# FloppyController1A.net
KiCad netlist of a schematic drawn in EAGLE
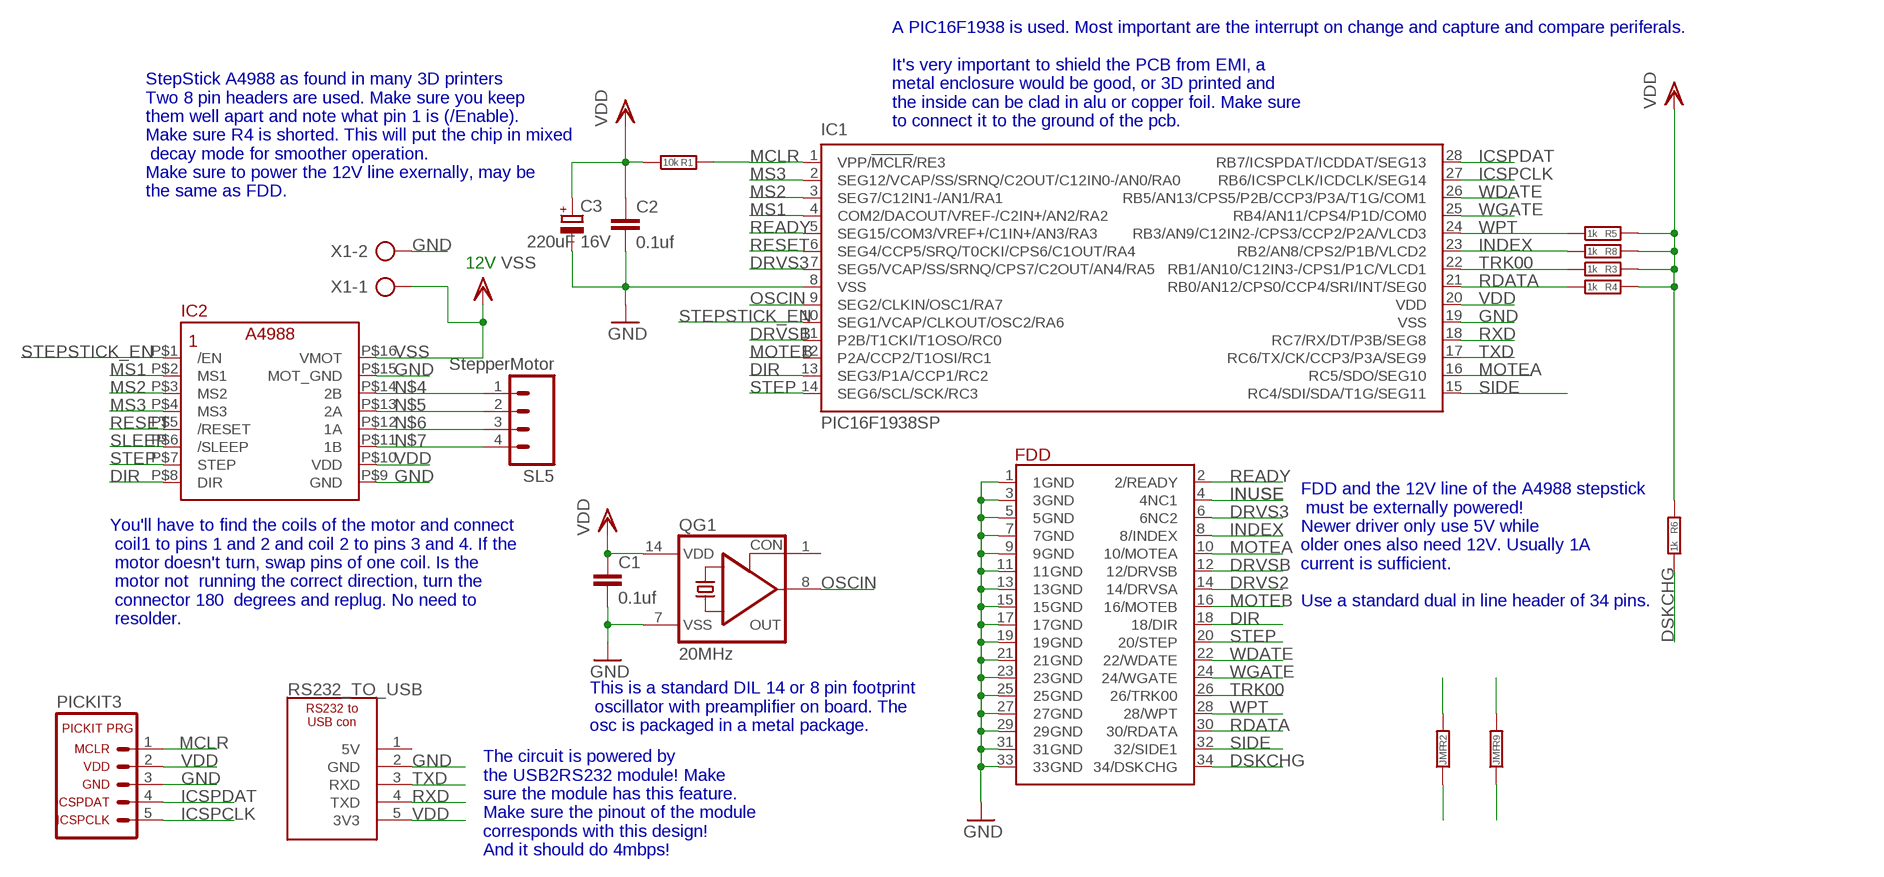
[diagram p0: schematic, sheet 1]

(export (version "E")
  (design (tool "Eeschema 10.0.6"))
  (components
    (comp (ref "C1")
      (value "0.1uf")
      (footprint "eagle-import:C0805TOP")
      (libsource (lib "eagle-import") (part "C-EUC0805BOTTOM"))
    )
    (comp (ref "C2")
      (value "0.1uf")
      (footprint "eagle-import:C0805TOP")
      (libsource (lib "eagle-import") (part "C-EUC0805BOTTOM"))
    )
    (comp (ref "C3")
      (value "220uF 16V")
      (footprint "eagle-import:E2,5-6")
      (libsource (lib "eagle-import") (part "CPOL-EUE2.5-6"))
    )
    (comp (ref "FDD")
      (value "FLOPPY_34PIN_CONN")
      (footprint "eagle-import:FLOPPY_34PIN_DUALROW")
      (libsource (lib "eagle-import") (part "FLOPPY_34PIN_CONN"))
    )
    (comp (ref "IC1")
      (value "PIC16F1938SP")
      (footprint "eagle-import:DIL28-3")
      (fields (field (name "MPN") "PIC16F1938-I/SP"))
      (libsource (lib "eagle-import") (part "PIC16F19SP38"))
    )
    (comp (ref "IC2")
      (value "STEPSTICK_A4988")
      (footprint "eagle-import:STEPSTICK_A4988")
      (libsource (lib "eagle-import") (part "STEPSTICK_A4988"))
    )
    (comp (ref "PICKIT3")
      (value "PICKIT3CONNECTOR")
      (footprint "eagle-import:05P")
      (libsource (lib "eagle-import") (part "PICKIT3CONNECTOR"))
    )
    (comp (ref "QG1")
      (value "20MHz")
      (footprint "eagle-import:SG51")
      (libsource (lib "eagle-import") (part "CRYSTAL_RES-SG51"))
    )
    (comp (ref "R1")
      (value "10k")
      (footprint "eagle-import:M1206")
      (libsource (lib "eagle-import") (part "R-EU_M1206"))
    )
    (comp (ref "R2")
      (value "JMP")
      (footprint "eagle-import:M1206")
      (libsource (lib "eagle-import") (part "R-EU_M1206"))
    )
    (comp (ref "R3")
      (value "1k")
      (footprint "eagle-import:M1206")
      (libsource (lib "eagle-import") (part "R-EU_M1206"))
    )
    (comp (ref "R4")
      (value "1k")
      (footprint "eagle-import:M1206")
      (libsource (lib "eagle-import") (part "R-EU_M1206"))
    )
    (comp (ref "R5")
      (value "1k")
      (footprint "eagle-import:M1206")
      (libsource (lib "eagle-import") (part "R-EU_M1206"))
    )
    (comp (ref "R6")
      (value "1k")
      (footprint "eagle-import:M1206")
      (libsource (lib "eagle-import") (part "R-EU_M1206"))
    )
    (comp (ref "R8")
      (value "1k")
      (footprint "eagle-import:M1206")
      (libsource (lib "eagle-import") (part "R-EU_M1206"))
    )
    (comp (ref "R9")
      (value "JMP")
      (footprint "eagle-import:M1206")
      (libsource (lib "eagle-import") (part "R-EU_M1206"))
    )
    (comp (ref "RS232_TO_USB")
      (value "RS232_TO_USB_CONNECTOR")
      (footprint "eagle-import:05P")
      (libsource (lib "eagle-import") (part "RS232_TO_USB_CONNECTOR"))
    )
    (comp (ref "SL5")
      (value "StepperMotor")
      (footprint "eagle-import:04P")
      (libsource (lib "eagle-import") (part "M04"))
    )
    (comp (ref "X1")
      (value "AK500/2-H")
      (footprint "eagle-import:AK500_2-H")
      (libsource (lib "eagle-import") (part "AK500/2-H"))
    )
  )
  (nets
    (net (code "1") (name "/DIR") (class "Default")
      (node (ref "FDD") (pin "18") (pinfunction "18/DIR_18") (pintype "input"))
      (node (ref "IC1") (pin "13") (pinfunction "SEG3/P1A/CCP1/RC2_13") (pintype "bidirectional"))
      (node (ref "IC2") (pin "P$8") (pinfunction "DIR_P$8") (pintype "input"))
    )
    (net (code "2") (name "/DRVS2") (class "Default")
      (node (ref "FDD") (pin "14") (pinfunction "14/DRVSA_14") (pintype "input"))
    )
    (net (code "3") (name "/DRVS3") (class "Default")
      (node (ref "FDD") (pin "6") (pinfunction "6NC2_6") (pintype "bidirectional"))
      (node (ref "IC1") (pin "7") (pinfunction "SEG5/VCAP/SS/SRNQ/CPS7/C2OUT/AN4/RA5_7") (pintype "bidirectional"))
    )
    (net (code "4") (name "/DRVSB") (class "Default")
      (node (ref "FDD") (pin "12") (pinfunction "12/DRVSB_12") (pintype "input"))
      (node (ref "IC1") (pin "11") (pinfunction "P2B/T1CKI/T1OSO/RC0_11") (pintype "bidirectional"))
    )
    (net (code "5") (name "/DSKCHG") (class "Default")
      (node (ref "FDD") (pin "34") (pinfunction "34/DSKCHG_34") (pintype "output"))
      (node (ref "R6") (pin "1") (pinfunction "1_1") (pintype "passive"))
    )
    (net (code "6") (name "/ICSPCLK") (class "Default")
      (node (ref "IC1") (pin "27") (pinfunction "RB6/ICSPCLK/ICDCLK/SEG14_27") (pintype "bidirectional"))
      (node (ref "PICKIT3") (pin "5") (pinfunction "5_ICSPCLK_5") (pintype "passive"))
    )
    (net (code "7") (name "/ICSPDAT") (class "Default")
      (node (ref "IC1") (pin "28") (pinfunction "RB7/ICSPDAT/ICDDAT/SEG13_28") (pintype "bidirectional"))
      (node (ref "PICKIT3") (pin "4") (pinfunction "4_ICSPDAT_4") (pintype "passive"))
    )
    (net (code "8") (name "/INDEX") (class "Default")
      (node (ref "FDD") (pin "8") (pinfunction "8/INDEX_8") (pintype "output"))
      (node (ref "IC1") (pin "23") (pinfunction "RB2/AN8/CPS2/P1B/VLCD2_23") (pintype "bidirectional"))
      (node (ref "R8") (pin "1") (pinfunction "1_1") (pintype "passive"))
    )
    (net (code "9") (name "/INUSE") (class "Default")
      (node (ref "FDD") (pin "4") (pinfunction "4NC1_4") (pintype "bidirectional"))
    )
    (net (code "10") (name "/MCLR") (class "Default")
      (node (ref "IC1") (pin "1") (pinfunction "VPP/~{MCLR}/RE3_1") (pintype "input"))
      (node (ref "PICKIT3") (pin "1") (pinfunction "1_MCLR_1") (pintype "passive"))
      (node (ref "R1") (pin "2") (pinfunction "2_2") (pintype "passive"))
    )
    (net (code "11") (name "/MOTEA") (class "Default")
      (node (ref "FDD") (pin "10") (pinfunction "10/MOTEA_10") (pintype "input"))
      (node (ref "IC1") (pin "16") (pinfunction "RC5/SDO/SEG10_16") (pintype "bidirectional"))
      (node (ref "R2") (pin "1") (pinfunction "1_1") (pintype "passive"))
      (node (ref "R2") (pin "2") (pinfunction "2_2") (pintype "passive"))
    )
    (net (code "12") (name "/MOTEB") (class "Default")
      (node (ref "FDD") (pin "16") (pinfunction "16/MOTEB_16") (pintype "input"))
      (node (ref "IC1") (pin "12") (pinfunction "P2A/CCP2/T1OSI/RC1_12") (pintype "bidirectional"))
    )
    (net (code "13") (name "/MS1") (class "Default")
      (node (ref "IC1") (pin "4") (pinfunction "COM2/DACOUT/VREF-/C2IN+/AN2/RA2_4") (pintype "bidirectional"))
      (node (ref "IC2") (pin "P$2") (pinfunction "MS1_P$2") (pintype "input"))
    )
    (net (code "14") (name "/MS2") (class "Default")
      (node (ref "IC1") (pin "3") (pinfunction "SEG7/C12IN1-/AN1/RA1_3") (pintype "bidirectional"))
      (node (ref "IC2") (pin "P$3") (pinfunction "MS2_P$3") (pintype "input"))
    )
    (net (code "15") (name "/MS3") (class "Default")
      (node (ref "IC1") (pin "2") (pinfunction "SEG12/VCAP/SS/SRNQ/C2OUT/C12IN0-/AN0/RA0_2") (pintype "bidirectional"))
      (node (ref "IC2") (pin "P$4") (pinfunction "MS3_P$4") (pintype "input"))
    )
    (net (code "16") (name "/N$4") (class "Default")
      (node (ref "IC2") (pin "P$14") (pinfunction "2B_P$14") (pintype "output"))
      (node (ref "SL5") (pin "1") (pinfunction "1_1") (pintype "passive"))
    )
    (net (code "17") (name "/N$5") (class "Default")
      (node (ref "IC2") (pin "P$13") (pinfunction "2A_P$13") (pintype "output"))
      (node (ref "SL5") (pin "2") (pinfunction "2_2") (pintype "passive"))
    )
    (net (code "18") (name "/N$6") (class "Default")
      (node (ref "IC2") (pin "P$12") (pinfunction "1A_P$12") (pintype "output"))
      (node (ref "SL5") (pin "3") (pinfunction "3_3") (pintype "passive"))
    )
    (net (code "19") (name "/N$7") (class "Default")
      (node (ref "IC2") (pin "P$11") (pinfunction "1B_P$11") (pintype "output"))
      (node (ref "SL5") (pin "4") (pinfunction "4_4") (pintype "passive"))
    )
    (net (code "20") (name "/OSCIN") (class "Default")
      (node (ref "IC1") (pin "9") (pinfunction "SEG2/CLKIN/OSC1/RA7_9") (pintype "bidirectional"))
      (node (ref "QG1") (pin "8") (pinfunction "OUT_8") (pintype "output"))
    )
    (net (code "21") (name "/RDATA") (class "Default")
      (node (ref "FDD") (pin "30") (pinfunction "30/RDATA_30") (pintype "output"))
      (node (ref "IC1") (pin "21") (pinfunction "RB0/AN12/CPS0/CCP4/SRI/INT/SEG0_21") (pintype "bidirectional"))
      (node (ref "R4") (pin "1") (pinfunction "1_1") (pintype "passive"))
    )
    (net (code "22") (name "/READY") (class "Default")
      (node (ref "FDD") (pin "2") (pinfunction "2/READY_2") (pintype "output"))
      (node (ref "IC1") (pin "5") (pinfunction "SEG15/COM3/VREF+/C1IN+/AN3/RA3_5") (pintype "bidirectional"))
    )
    (net (code "23") (name "/RESET") (class "Default")
      (node (ref "IC1") (pin "6") (pinfunction "SEG4/CCP5/SRQ/T0CKI/CPS6/C1OUT/RA4_6") (pintype "bidirectional"))
      (node (ref "IC2") (pin "P$5") (pinfunction "/RESET_P$5") (pintype "input"))
    )
    (net (code "24") (name "/RXD") (class "Default")
      (node (ref "IC1") (pin "18") (pinfunction "RC7/RX/DT/P3B/SEG8_18") (pintype "bidirectional"))
      (node (ref "RS232_TO_USB") (pin "4") (pinfunction "TXD_4") (pintype "bidirectional"))
    )
    (net (code "25") (name "/SIDE") (class "Default")
      (node (ref "FDD") (pin "32") (pinfunction "32/SIDE1_32") (pintype "input"))
      (node (ref "IC1") (pin "15") (pinfunction "RC4/SDI/SDA/T1G/SEG11_15") (pintype "bidirectional"))
    )
    (net (code "26") (name "/SLEEP") (class "Default")
      (node (ref "IC2") (pin "P$6") (pinfunction "/SLEEP_P$6") (pintype "input"))
    )
    (net (code "27") (name "/STEP") (class "Default")
      (node (ref "FDD") (pin "20") (pinfunction "20/STEP_20") (pintype "input"))
      (node (ref "IC1") (pin "14") (pinfunction "SEG6/SCL/SCK/RC3_14") (pintype "bidirectional"))
      (node (ref "IC2") (pin "P$7") (pinfunction "STEP_P$7") (pintype "input"))
    )
    (net (code "28") (name "/STEPSTICK_EN") (class "Default")
      (node (ref "IC1") (pin "10") (pinfunction "SEG1/VCAP/CLKOUT/OSC2/RA6_10") (pintype "bidirectional"))
      (node (ref "IC2") (pin "P$1") (pinfunction "/EN_P$1") (pintype "input"))
    )
    (net (code "29") (name "/TRK00") (class "Default")
      (node (ref "FDD") (pin "26") (pinfunction "26/TRK00_26") (pintype "output"))
      (node (ref "IC1") (pin "22") (pinfunction "RB1/AN10/C12IN3-/CPS1/P1C/VLCD1_22") (pintype "bidirectional"))
      (node (ref "R3") (pin "1") (pinfunction "1_1") (pintype "passive"))
    )
    (net (code "30") (name "/TXD") (class "Default")
      (node (ref "IC1") (pin "17") (pinfunction "RC6/TX/CK/CCP3/P3A/SEG9_17") (pintype "bidirectional"))
      (node (ref "RS232_TO_USB") (pin "3") (pinfunction "RXD_3") (pintype "bidirectional"))
    )
    (net (code "31") (name "/WDATE") (class "Default")
      (node (ref "FDD") (pin "22") (pinfunction "22/WDATE_22") (pintype "input"))
      (node (ref "IC1") (pin "26") (pinfunction "RB5/AN13/CPS5/P2B/CCP3/P3A/T1G/COM1_26") (pintype "bidirectional"))
    )
    (net (code "32") (name "/WGATE") (class "Default")
      (node (ref "FDD") (pin "24") (pinfunction "24/WGATE_24") (pintype "input"))
      (node (ref "IC1") (pin "25") (pinfunction "RB4/AN11/CPS4/P1D/COM0_25") (pintype "bidirectional"))
    )
    (net (code "33") (name "/WPT") (class "Default")
      (node (ref "FDD") (pin "28") (pinfunction "28/WPT_28") (pintype "output"))
      (node (ref "IC1") (pin "24") (pinfunction "RB3/AN9/C12IN2-/CPS3/CCP2/P2A/VLCD3_24") (pintype "bidirectional"))
      (node (ref "R5") (pin "1") (pinfunction "1_1") (pintype "passive"))
    )
    (net (code "34") (name "GND") (class "Default")
      (node (ref "C1") (pin "2") (pinfunction "2_2") (pintype "passive"))
      (node (ref "C2") (pin "2") (pinfunction "2_2") (pintype "passive"))
      (node (ref "C3") (pin "-") (pinfunction "-_-") (pintype "passive"))
      (node (ref "FDD") (pin "1") (pinfunction "1GND_1") (pintype "power_in"))
      (node (ref "FDD") (pin "11") (pinfunction "11GND_11") (pintype "power_in"))
      (node (ref "FDD") (pin "13") (pinfunction "13GND_13") (pintype "power_in"))
      (node (ref "FDD") (pin "15") (pinfunction "15GND_15") (pintype "power_in"))
      (node (ref "FDD") (pin "17") (pinfunction "17GND_17") (pintype "power_in"))
      (node (ref "FDD") (pin "19") (pinfunction "19GND_19") (pintype "power_in"))
      (node (ref "FDD") (pin "21") (pinfunction "21GND_21") (pintype "power_in"))
      (node (ref "FDD") (pin "23") (pinfunction "23GND_23") (pintype "power_in"))
      (node (ref "FDD") (pin "25") (pinfunction "25GND_25") (pintype "power_in"))
      (node (ref "FDD") (pin "27") (pinfunction "27GND_27") (pintype "power_in"))
      (node (ref "FDD") (pin "29") (pinfunction "29GND_29") (pintype "power_in"))
      (node (ref "FDD") (pin "3") (pinfunction "3GND_3") (pintype "power_in"))
      (node (ref "FDD") (pin "31") (pinfunction "31GND_31") (pintype "power_in"))
      (node (ref "FDD") (pin "33") (pinfunction "33GND_33") (pintype "power_in"))
      (node (ref "FDD") (pin "5") (pinfunction "5GND_5") (pintype "power_in"))
      (node (ref "FDD") (pin "7") (pinfunction "7GND_7") (pintype "power_in"))
      (node (ref "FDD") (pin "9") (pinfunction "9GND_9") (pintype "power_in"))
      (node (ref "IC1") (pin "19") (pinfunction "VSS_19") (pintype "power_in"))
      (node (ref "IC1") (pin "8") (pinfunction "VSS_8") (pintype "power_in"))
      (node (ref "IC2") (pin "P$15") (pinfunction "MOT_GND_P$15") (pintype "power_in"))
      (node (ref "IC2") (pin "P$9") (pinfunction "GND_P$9") (pintype "power_in"))
      (node (ref "PICKIT3") (pin "3") (pinfunction "3_GND_3") (pintype "passive"))
      (node (ref "QG1") (pin "7") (pinfunction "VSS_7") (pintype "power_in"))
      (node (ref "R9") (pin "1") (pinfunction "1_1") (pintype "passive"))
      (node (ref "R9") (pin "2") (pinfunction "2_2") (pintype "passive"))
      (node (ref "RS232_TO_USB") (pin "2") (pinfunction "GND_2") (pintype "bidirectional"))
      (node (ref "X1") (pin "2") (pinfunction "KL_2") (pintype "passive"))
    )
    (net (code "35") (name "VDD") (class "Default")
      (node (ref "C1") (pin "1") (pinfunction "1_1") (pintype "passive"))
      (node (ref "C2") (pin "1") (pinfunction "1_1") (pintype "passive"))
      (node (ref "C3") (pin "+") (pinfunction "+_+") (pintype "passive"))
      (node (ref "IC1") (pin "20") (pinfunction "VDD_20") (pintype "power_in"))
      (node (ref "IC2") (pin "P$10") (pinfunction "VDD_P$10") (pintype "power_in"))
      (node (ref "PICKIT3") (pin "2") (pinfunction "2_VDD_2") (pintype "passive"))
      (node (ref "QG1") (pin "14") (pinfunction "VDD_14") (pintype "power_in"))
      (node (ref "R1") (pin "1") (pinfunction "1_1") (pintype "passive"))
      (node (ref "R3") (pin "2") (pinfunction "2_2") (pintype "passive"))
      (node (ref "R4") (pin "2") (pinfunction "2_2") (pintype "passive"))
      (node (ref "R5") (pin "2") (pinfunction "2_2") (pintype "passive"))
      (node (ref "R6") (pin "2") (pinfunction "2_2") (pintype "passive"))
      (node (ref "R8") (pin "2") (pinfunction "2_2") (pintype "passive"))
      (node (ref "RS232_TO_USB") (pin "5") (pinfunction "3V3_5") (pintype "bidirectional"))
    )
    (net (code "36") (name "VSS") (class "Default")
      (node (ref "IC2") (pin "P$16") (pinfunction "VMOT_P$16") (pintype "power_in"))
      (node (ref "X1") (pin "1") (pinfunction "KL_1") (pintype "passive"))
    )
    (net (code "37") (name "unconnected-(QG1-CON-Pad1)") (class "Default")
      (node (ref "QG1") (pin "1") (pinfunction "CON_1") (pintype "input"))
    )
    (net (code "38") (name "unconnected-(RS232_TO_USB-5V-Pad1)") (class "Default")
      (node (ref "RS232_TO_USB") (pin "1") (pinfunction "5V_1") (pintype "bidirectional"))
    )
  )
)
